# PWM_OUTS.net
KiCad netlist of a schematic drawn in Altium Designer
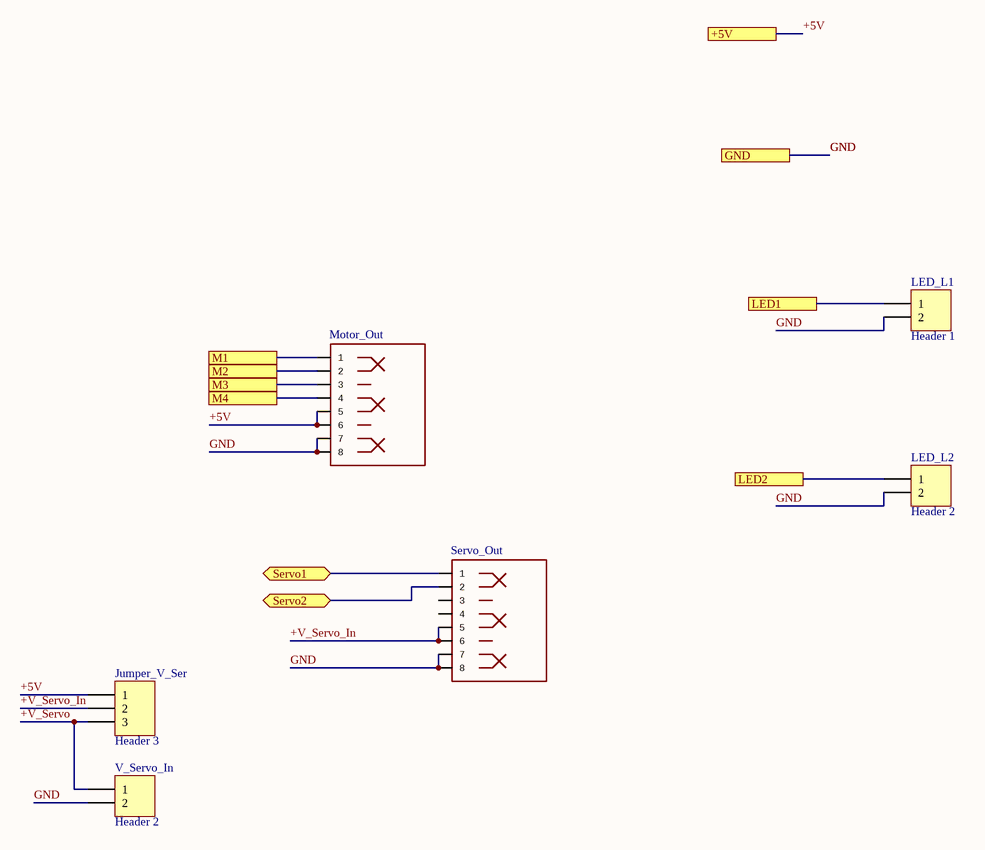
[diagram p0: PWM_OUTS.SchDoc]

(export (version "E")
  (design (tool "Eeschema 10.0.6"))
  (components
    (comp (ref "Jumper_V_Ser")
      (value "Header 3")
      (footprint "HDR1X3")
      (description "Header, 3-Pin")
      (fields (field (name "PUBLISHER") "Altium Limited"))
      (libsource (lib "Miscellaneous Connectors") (part "Header 3"))
    )
    (comp (ref "LED_L1")
      (value "Header 1")
      (footprint "HDR1X2")
      (description "Header, 2-Pin")
      (fields (field (name "PUBLISHER") "Altium Limited"))
      (libsource (lib "Miscellaneous Connectors") (part "Header 2"))
    )
    (comp (ref "LED_L2")
      (value "Header 2")
      (footprint "HDR1X2")
      (description "Header, 2-Pin")
      (fields (field (name "PUBLISHER") "Altium Limited"))
      (libsource (lib "Miscellaneous Connectors") (part "Header 2"))
    )
    (comp (ref "Motor_Out")
      (value "~")
      (footprint "RJ45-8")
      (libsource (lib "SparkFun-Connectors") (part "RJ45-8PTH"))
    )
    (comp (ref "Servo_Out")
      (value "~")
      (footprint "RJ45-8")
      (libsource (lib "SparkFun-Connectors") (part "RJ45-8PTH"))
    )
    (comp (ref "V_Servo_In")
      (value "Header 2")
      (footprint "HDR1X2")
      (description "Header, 2-Pin")
      (fields (field (name "PUBLISHER") "Altium Limited"))
      (libsource (lib "Miscellaneous Connectors") (part "Header 2"))
    )
  )
  (nets
    (net (code "1") (name "/+5V") (class "Default")
      (node (ref "Jumper_V_Ser") (pin "1") (pinfunction "1_1") (pintype "passive"))
      (node (ref "Motor_Out") (pin "5") (pinfunction "5_5") (pintype "passive"))
      (node (ref "Motor_Out") (pin "6") (pinfunction "6_6") (pintype "passive"))
    )
    (net (code "2") (name "/+V_Servo") (class "Default")
      (node (ref "Jumper_V_Ser") (pin "3") (pinfunction "3_3") (pintype "passive"))
      (node (ref "V_Servo_In") (pin "1") (pinfunction "1_1") (pintype "passive"))
    )
    (net (code "3") (name "/+V_Servo_In") (class "Default")
      (node (ref "Jumper_V_Ser") (pin "2") (pinfunction "2_2") (pintype "passive"))
      (node (ref "Servo_Out") (pin "5") (pinfunction "5_5") (pintype "passive"))
      (node (ref "Servo_Out") (pin "6") (pinfunction "6_6") (pintype "passive"))
    )
    (net (code "4") (name "/GND") (class "Default")
      (node (ref "LED_L1") (pin "2") (pinfunction "2_2") (pintype "passive"))
      (node (ref "LED_L2") (pin "2") (pinfunction "2_2") (pintype "passive"))
      (node (ref "Motor_Out") (pin "7") (pinfunction "7_7") (pintype "passive"))
      (node (ref "Motor_Out") (pin "8") (pinfunction "8_8") (pintype "passive"))
      (node (ref "Servo_Out") (pin "7") (pinfunction "7_7") (pintype "passive"))
      (node (ref "Servo_Out") (pin "8") (pinfunction "8_8") (pintype "passive"))
      (node (ref "V_Servo_In") (pin "2") (pinfunction "2_2") (pintype "passive"))
    )
    (net (code "5") (name "/LED1") (class "Default")
      (node (ref "LED_L1") (pin "1") (pinfunction "1_1") (pintype "passive"))
    )
    (net (code "6") (name "/LED2") (class "Default")
      (node (ref "LED_L2") (pin "1") (pinfunction "1_1") (pintype "passive"))
    )
    (net (code "7") (name "/M1") (class "Default")
      (node (ref "Motor_Out") (pin "1") (pinfunction "1_1") (pintype "passive"))
    )
    (net (code "8") (name "/M2") (class "Default")
      (node (ref "Motor_Out") (pin "2") (pinfunction "2_2") (pintype "passive"))
    )
    (net (code "9") (name "/M3") (class "Default")
      (node (ref "Motor_Out") (pin "3") (pinfunction "3_3") (pintype "passive"))
    )
    (net (code "10") (name "/M4") (class "Default")
      (node (ref "Motor_Out") (pin "4") (pinfunction "4_4") (pintype "passive"))
    )
    (net (code "11") (name "/Servo1") (class "Default")
      (node (ref "Servo_Out") (pin "1") (pinfunction "1_1") (pintype "passive"))
    )
    (net (code "12") (name "/Servo2") (class "Default")
      (node (ref "Servo_Out") (pin "2") (pinfunction "2_2") (pintype "passive"))
    )
    (net (code "13") (name "unconnected-(Servo_Out-Pad3)") (class "Default")
      (node (ref "Servo_Out") (pin "3") (pinfunction "3_3") (pintype "passive"))
    )
    (net (code "14") (name "unconnected-(Servo_Out-Pad4)") (class "Default")
      (node (ref "Servo_Out") (pin "4") (pinfunction "4_4") (pintype "passive"))
    )
  )
)
